# CC2530.net
KiCad netlist of a schematic drawn in Altium Designer
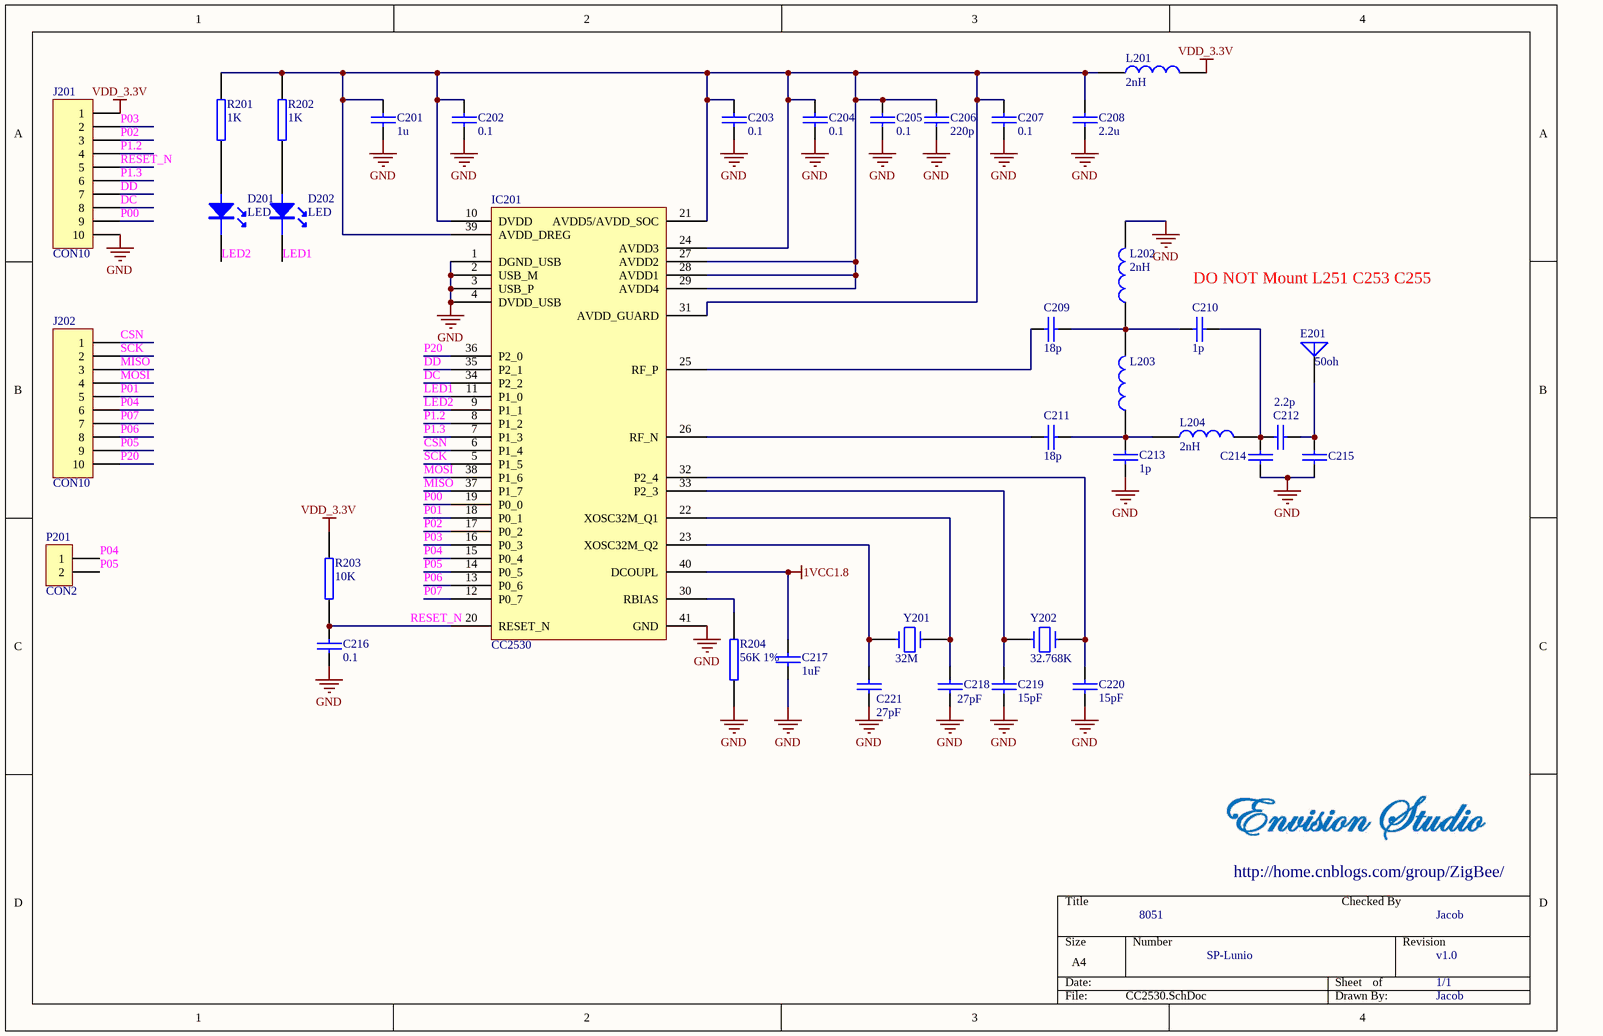
[diagram p0: CC2530.SchDoc]

(export (version "E")
  (design (tool "Eeschema 10.0.6"))
  (components
    (comp (ref "C201")
      (value "1u")
      (footprint "0402")
      (description "Capacitor")
      (libsource (lib "Miscellaneous Devices") (part "CAP"))
    )
    (comp (ref "C202")
      (value "0.1")
      (footprint "0402")
      (description "Capacitor")
      (libsource (lib "Miscellaneous Devices") (part "CAP"))
    )
    (comp (ref "C203")
      (value "0.1")
      (footprint "0402")
      (description "Capacitor")
      (libsource (lib "Miscellaneous Devices") (part "CAP"))
    )
    (comp (ref "C204")
      (value "0.1")
      (footprint "0402")
      (description "Capacitor")
      (libsource (lib "Miscellaneous Devices") (part "CAP"))
    )
    (comp (ref "C205")
      (value "0.1")
      (footprint "0402")
      (description "Capacitor")
      (libsource (lib "Miscellaneous Devices") (part "CAP"))
    )
    (comp (ref "C206")
      (value "220p")
      (footprint "0402")
      (description "Capacitor")
      (libsource (lib "Miscellaneous Devices") (part "CAP"))
    )
    (comp (ref "C207")
      (value "0.1")
      (footprint "0402")
      (description "Capacitor")
      (libsource (lib "Miscellaneous Devices") (part "CAP"))
    )
    (comp (ref "C208")
      (value "2.2u")
      (footprint "0402")
      (description "Capacitor")
      (libsource (lib "Miscellaneous Devices") (part "CAP"))
    )
    (comp (ref "C209")
      (value "18p")
      (footprint "0402")
      (description "Capacitor")
      (libsource (lib "Miscellaneous Devices") (part "CAP"))
    )
    (comp (ref "C210")
      (value "1p")
      (footprint "0402")
      (description "Capacitor")
      (libsource (lib "Miscellaneous Devices") (part "CAP"))
    )
    (comp (ref "C211")
      (value "18p")
      (footprint "0402")
      (description "Capacitor")
      (libsource (lib "Miscellaneous Devices") (part "CAP"))
    )
    (comp (ref "C212")
      (value "2.2p")
      (footprint "0402")
      (description "Capacitor")
      (libsource (lib "Miscellaneous Devices") (part "CAP"))
    )
    (comp (ref "C213")
      (value "1p")
      (footprint "0402")
      (description "Capacitor")
      (libsource (lib "Miscellaneous Devices") (part "CAP"))
    )
    (comp (ref "C214")
      (value "~")
      (footprint "0402")
      (description "Capacitor")
      (libsource (lib "Miscellaneous Devices") (part "CAP"))
    )
    (comp (ref "C215")
      (value "~")
      (footprint "0402")
      (description "Capacitor")
      (libsource (lib "Miscellaneous Devices") (part "CAP"))
    )
    (comp (ref "C216")
      (value "0.1")
      (footprint "0402")
      (description "Capacitor")
      (libsource (lib "Miscellaneous Devices") (part "CAP"))
    )
    (comp (ref "C217")
      (value "1uF")
      (footprint "0402")
      (description "Capacitor")
      (libsource (lib "Miscellaneous Devices") (part "CAP"))
    )
    (comp (ref "C218")
      (value "27pF")
      (footprint "0402")
      (description "Capacitor")
      (libsource (lib "Miscellaneous Devices") (part "CAP"))
    )
    (comp (ref "C219")
      (value "15pF")
      (footprint "0402")
      (description "Capacitor")
      (libsource (lib "Miscellaneous Devices") (part "CAP"))
    )
    (comp (ref "C220")
      (value "15pF")
      (footprint "0402")
      (description "Capacitor")
      (libsource (lib "Miscellaneous Devices") (part "CAP"))
    )
    (comp (ref "C221")
      (value "27pF")
      (footprint "0402")
      (description "Capacitor")
      (libsource (lib "Miscellaneous Devices") (part "CAP"))
    )
    (comp (ref "D201")
      (value "LED")
      (footprint "LED-0603")
      (libsource (lib "Miscellaneous Devices") (part "LED"))
    )
    (comp (ref "D202")
      (value "LED")
      (footprint "LED-0603")
      (libsource (lib "Miscellaneous Devices") (part "LED"))
    )
    (comp (ref "E201")
      (value "50oh")
      (footprint "ANT")
      (description "Generic Antenna")
      (libsource (lib "Miscellaneous Devices") (part "ANTENNA"))
    )
    (comp (ref "IC201") (value "CC2530") (footprint "PVQFN-N40") (libsource (lib "集成") (part "CC2530")))
    (comp (ref "J201")
      (value "CON10")
      (footprint "SIP10-2.0")
      (description "Connector")
      (libsource (lib "Miscellaneous Devices") (part "CON10"))
    )
    (comp (ref "J202")
      (value "CON10")
      (footprint "SIP10-2.0")
      (description "Connector")
      (libsource (lib "Miscellaneous Devices") (part "CON10"))
    )
    (comp (ref "L201")
      (value "2nH")
      (footprint "0402")
      (libsource (lib "Miscellaneous Devices") (part "INDUCTOR"))
    )
    (comp (ref "L202")
      (value "2nH")
      (footprint "0402")
      (libsource (lib "Miscellaneous Devices") (part "INDUCTOR"))
    )
    (comp (ref "L203")
      (value "~")
      (footprint "0402")
      (libsource (lib "Miscellaneous Devices") (part "INDUCTOR"))
    )
    (comp (ref "L204")
      (value "2nH")
      (footprint "0402")
      (libsource (lib "Miscellaneous Devices") (part "INDUCTOR"))
    )
    (comp (ref "P201")
      (value "CON2")
      (footprint "SIP2")
      (description "Connector")
      (libsource (lib "Miscellaneous Devices_99se") (part "CON2"))
    )
    (comp (ref "R201")
      (value "1K")
      (footprint "0402")
      (libsource (lib "Miscellaneous Devices") (part "RES2"))
    )
    (comp (ref "R202")
      (value "1K")
      (footprint "0402")
      (libsource (lib "Miscellaneous Devices") (part "RES2"))
    )
    (comp (ref "R203")
      (value "10K")
      (footprint "0402")
      (libsource (lib "Miscellaneous Devices") (part "RES2"))
    )
    (comp (ref "R204")
      (value "56K 1%")
      (footprint "0402")
      (libsource (lib "Miscellaneous Devices") (part "RES2"))
    )
    (comp (ref "Y201")
      (value "32M")
      (footprint "XT-SMD3225")
      (description "Crystal")
      (libsource (lib "Miscellaneous Devices") (part "CRYSTAL"))
    )
    (comp (ref "Y202")
      (value "32.768K")
      (footprint "XT_3")
      (description "Crystal")
      (libsource (lib "Miscellaneous Devices") (part "CRYSTAL"))
    )
  )
  (nets
    (net (code "1") (name "/CSN") (class "Default")
      (node (ref "IC201") (pin "6") (pinfunction "P1_4_6") (pintype "passive"))
      (node (ref "J202") (pin "1") (pinfunction "1_1") (pintype "passive"))
    )
    (net (code "2") (name "/DC") (class "Default")
      (node (ref "IC201") (pin "34") (pinfunction "P2_2_34") (pintype "passive"))
      (node (ref "J201") (pin "8") (pinfunction "8_8") (pintype "passive"))
    )
    (net (code "3") (name "/DD") (class "Default")
      (node (ref "IC201") (pin "35") (pinfunction "P2_1_35") (pintype "passive"))
      (node (ref "J201") (pin "7") (pinfunction "7_7") (pintype "passive"))
    )
    (net (code "4") (name "/LED1") (class "Default")
      (node (ref "D202") (pin "K") (pinfunction "2_K") (pintype "passive"))
      (node (ref "IC201") (pin "11") (pinfunction "P1_0_11") (pintype "passive"))
    )
    (net (code "5") (name "/LED2") (class "Default")
      (node (ref "D201") (pin "K") (pinfunction "2_K") (pintype "passive"))
      (node (ref "IC201") (pin "9") (pinfunction "P1_1_9") (pintype "passive"))
    )
    (net (code "6") (name "/MISO") (class "Default")
      (node (ref "IC201") (pin "37") (pinfunction "P1_7_37") (pintype "passive"))
      (node (ref "J202") (pin "3") (pinfunction "3_3") (pintype "passive"))
    )
    (net (code "7") (name "/MOSI") (class "Default")
      (node (ref "IC201") (pin "38") (pinfunction "P1_6_38") (pintype "passive"))
      (node (ref "J202") (pin "4") (pinfunction "4_4") (pintype "passive"))
    )
    (net (code "8") (name "/P00") (class "Default")
      (node (ref "IC201") (pin "19") (pinfunction "P0_0_19") (pintype "passive"))
      (node (ref "J201") (pin "9") (pinfunction "9_9") (pintype "passive"))
    )
    (net (code "9") (name "/P01") (class "Default")
      (node (ref "IC201") (pin "18") (pinfunction "P0_1_18") (pintype "passive"))
      (node (ref "J202") (pin "5") (pinfunction "5_5") (pintype "passive"))
    )
    (net (code "10") (name "/P1.2") (class "Default")
      (node (ref "IC201") (pin "8") (pinfunction "P1_2_8") (pintype "passive"))
      (node (ref "J201") (pin "4") (pinfunction "4_4") (pintype "passive"))
    )
    (net (code "11") (name "/P1.3") (class "Default")
      (node (ref "IC201") (pin "7") (pinfunction "P1_3_7") (pintype "passive"))
      (node (ref "J201") (pin "6") (pinfunction "6_6") (pintype "passive"))
    )
    (net (code "12") (name "/P02") (class "Default")
      (node (ref "IC201") (pin "17") (pinfunction "P0_2_17") (pintype "passive"))
      (node (ref "J201") (pin "3") (pinfunction "3_3") (pintype "passive"))
    )
    (net (code "13") (name "/P03") (class "Default")
      (node (ref "IC201") (pin "16") (pinfunction "P0_3_16") (pintype "passive"))
      (node (ref "J201") (pin "2") (pinfunction "2_2") (pintype "passive"))
    )
    (net (code "14") (name "/P04") (class "Default")
      (node (ref "IC201") (pin "15") (pinfunction "P0_4_15") (pintype "passive"))
      (node (ref "J202") (pin "6") (pinfunction "6_6") (pintype "passive"))
      (node (ref "P201") (pin "1") (pinfunction "1_1") (pintype "passive"))
    )
    (net (code "15") (name "/P05") (class "Default")
      (node (ref "IC201") (pin "14") (pinfunction "P0_5_14") (pintype "passive"))
      (node (ref "J202") (pin "9") (pinfunction "9_9") (pintype "passive"))
      (node (ref "P201") (pin "2") (pinfunction "2_2") (pintype "passive"))
    )
    (net (code "16") (name "/P06") (class "Default")
      (node (ref "IC201") (pin "13") (pinfunction "P0_6_13") (pintype "passive"))
      (node (ref "J202") (pin "8") (pinfunction "8_8") (pintype "passive"))
    )
    (net (code "17") (name "/P07") (class "Default")
      (node (ref "IC201") (pin "12") (pinfunction "P0_7_12") (pintype "passive"))
      (node (ref "J202") (pin "7") (pinfunction "7_7") (pintype "passive"))
    )
    (net (code "18") (name "/P20") (class "Default")
      (node (ref "IC201") (pin "36") (pinfunction "P2_0_36") (pintype "passive"))
      (node (ref "J202") (pin "10") (pinfunction "10_10") (pintype "passive"))
    )
    (net (code "19") (name "/RESET_N") (class "Default")
      (node (ref "C216") (pin "1") (pinfunction "1_1") (pintype "passive"))
      (node (ref "IC201") (pin "20") (pinfunction "RESET_N_20") (pintype "passive"))
      (node (ref "J201") (pin "5") (pinfunction "5_5") (pintype "passive"))
      (node (ref "R203") (pin "1") (pinfunction "1_1") (pintype "passive"))
    )
    (net (code "20") (name "/SCK") (class "Default")
      (node (ref "IC201") (pin "5") (pinfunction "P1_5_5") (pintype "passive"))
      (node (ref "J202") (pin "2") (pinfunction "2_2") (pintype "passive"))
    )
    (net (code "21") (name "1VCC1.8") (class "Default")
      (node (ref "C217") (pin "1") (pinfunction "1_1") (pintype "passive"))
      (node (ref "IC201") (pin "40") (pinfunction "DCOUPL_40") (pintype "passive"))
    )
    (net (code "22") (name "GND") (class "Default")
      (node (ref "C201") (pin "2") (pinfunction "2_2") (pintype "passive"))
      (node (ref "C202") (pin "2") (pinfunction "2_2") (pintype "passive"))
      (node (ref "C203") (pin "2") (pinfunction "2_2") (pintype "passive"))
      (node (ref "C204") (pin "2") (pinfunction "2_2") (pintype "passive"))
      (node (ref "C205") (pin "2") (pinfunction "2_2") (pintype "passive"))
      (node (ref "C206") (pin "2") (pinfunction "2_2") (pintype "passive"))
      (node (ref "C207") (pin "2") (pinfunction "2_2") (pintype "passive"))
      (node (ref "C208") (pin "2") (pinfunction "2_2") (pintype "passive"))
      (node (ref "C213") (pin "2") (pinfunction "2_2") (pintype "passive"))
      (node (ref "C214") (pin "2") (pinfunction "2_2") (pintype "passive"))
      (node (ref "C215") (pin "1") (pinfunction "1_1") (pintype "passive"))
      (node (ref "C216") (pin "2") (pinfunction "2_2") (pintype "passive"))
      (node (ref "C217") (pin "2") (pinfunction "2_2") (pintype "passive"))
      (node (ref "C218") (pin "2") (pinfunction "2_2") (pintype "passive"))
      (node (ref "C219") (pin "2") (pinfunction "2_2") (pintype "passive"))
      (node (ref "C220") (pin "2") (pinfunction "2_2") (pintype "passive"))
      (node (ref "C221") (pin "2") (pinfunction "2_2") (pintype "passive"))
      (node (ref "IC201") (pin "1") (pinfunction "DGND_USB_1") (pintype "passive"))
      (node (ref "IC201") (pin "2") (pinfunction "USB_M_2") (pintype "passive"))
      (node (ref "IC201") (pin "3") (pinfunction "USB_P_3") (pintype "passive"))
      (node (ref "IC201") (pin "4") (pinfunction "DVDD_USB_4") (pintype "passive"))
      (node (ref "IC201") (pin "41") (pinfunction "GND_41") (pintype "passive"))
      (node (ref "J201") (pin "10") (pinfunction "10_10") (pintype "passive"))
      (node (ref "L202") (pin "2") (pinfunction "2_2") (pintype "passive"))
      (node (ref "R204") (pin "2") (pinfunction "2_2") (pintype "passive"))
    )
    (net (code "23") (name "Net-(C209-Pad2)") (class "Default")
      (node (ref "C209") (pin "2") (pinfunction "2_2") (pintype "passive"))
      (node (ref "C210") (pin "1") (pinfunction "1_1") (pintype "passive"))
      (node (ref "L202") (pin "1") (pinfunction "1_1") (pintype "passive"))
      (node (ref "L203") (pin "2") (pinfunction "2_2") (pintype "passive"))
    )
    (net (code "24") (name "Net-(C210-Pad2)") (class "Default")
      (node (ref "C210") (pin "2") (pinfunction "2_2") (pintype "passive"))
      (node (ref "C212") (pin "1") (pinfunction "1_1") (pintype "passive"))
      (node (ref "C214") (pin "1") (pinfunction "1_1") (pintype "passive"))
      (node (ref "L204") (pin "2") (pinfunction "2_2") (pintype "passive"))
    )
    (net (code "25") (name "Net-(C211-Pad2)") (class "Default")
      (node (ref "C211") (pin "2") (pinfunction "2_2") (pintype "passive"))
      (node (ref "C213") (pin "1") (pinfunction "1_1") (pintype "passive"))
      (node (ref "L203") (pin "1") (pinfunction "1_1") (pintype "passive"))
      (node (ref "L204") (pin "1") (pinfunction "1_1") (pintype "passive"))
    )
    (net (code "26") (name "Net-(D201-1)") (class "Default")
      (node (ref "D201") (pin "A") (pinfunction "1_A") (pintype "passive"))
      (node (ref "R201") (pin "1") (pinfunction "1_1") (pintype "passive"))
    )
    (net (code "27") (name "Net-(D202-1)") (class "Default")
      (node (ref "D202") (pin "A") (pinfunction "1_A") (pintype "passive"))
      (node (ref "R202") (pin "1") (pinfunction "1_1") (pintype "passive"))
    )
    (net (code "28") (name "Net-(E201-A)") (class "Default")
      (node (ref "C212") (pin "2") (pinfunction "2_2") (pintype "passive"))
      (node (ref "C215") (pin "2") (pinfunction "2_2") (pintype "passive"))
      (node (ref "E201") (pin "1") (pinfunction "A_1") (pintype "passive"))
    )
    (net (code "29") (name "Net-(IC201-AVDD1)") (class "Default")
      (node (ref "C201") (pin "1") (pinfunction "1_1") (pintype "passive"))
      (node (ref "C202") (pin "1") (pinfunction "1_1") (pintype "passive"))
      (node (ref "C203") (pin "1") (pinfunction "1_1") (pintype "passive"))
      (node (ref "C204") (pin "1") (pinfunction "1_1") (pintype "passive"))
      (node (ref "C205") (pin "1") (pinfunction "1_1") (pintype "passive"))
      (node (ref "C206") (pin "1") (pinfunction "1_1") (pintype "passive"))
      (node (ref "C207") (pin "1") (pinfunction "1_1") (pintype "passive"))
      (node (ref "C208") (pin "1") (pinfunction "1_1") (pintype "passive"))
      (node (ref "IC201") (pin "10") (pinfunction "DVDD_10") (pintype "passive"))
      (node (ref "IC201") (pin "21") (pinfunction "AVDD5/AVDD_SOC_21") (pintype "passive"))
      (node (ref "IC201") (pin "24") (pinfunction "AVDD3_24") (pintype "passive"))
      (node (ref "IC201") (pin "27") (pinfunction "AVDD2_27") (pintype "passive"))
      (node (ref "IC201") (pin "28") (pinfunction "AVDD1_28") (pintype "passive"))
      (node (ref "IC201") (pin "29") (pinfunction "AVDD4_29") (pintype "passive"))
      (node (ref "IC201") (pin "31") (pinfunction "AVDD_GUARD_31") (pintype "passive"))
      (node (ref "IC201") (pin "39") (pinfunction "AVDD_DREG_39") (pintype "passive"))
      (node (ref "L201") (pin "1") (pinfunction "1_1") (pintype "passive"))
      (node (ref "R201") (pin "2") (pinfunction "2_2") (pintype "passive"))
      (node (ref "R202") (pin "2") (pinfunction "2_2") (pintype "passive"))
    )
    (net (code "30") (name "Net-(IC201-P2_3)") (class "Default")
      (node (ref "C219") (pin "1") (pinfunction "1_1") (pintype "passive"))
      (node (ref "IC201") (pin "33") (pinfunction "P2_3_33") (pintype "passive"))
      (node (ref "Y202") (pin "2") (pinfunction "2_2") (pintype "passive"))
    )
    (net (code "31") (name "Net-(IC201-P2_4)") (class "Default")
      (node (ref "C220") (pin "1") (pinfunction "1_1") (pintype "passive"))
      (node (ref "IC201") (pin "32") (pinfunction "P2_4_32") (pintype "passive"))
      (node (ref "Y202") (pin "1") (pinfunction "1_1") (pintype "passive"))
    )
    (net (code "32") (name "Net-(IC201-RBIAS)") (class "Default")
      (node (ref "IC201") (pin "30") (pinfunction "RBIAS_30") (pintype "passive"))
      (node (ref "R204") (pin "1") (pinfunction "1_1") (pintype "passive"))
    )
    (net (code "33") (name "Net-(IC201-RF_N)") (class "Default")
      (node (ref "C211") (pin "1") (pinfunction "1_1") (pintype "passive"))
      (node (ref "IC201") (pin "26") (pinfunction "RF_N_26") (pintype "passive"))
    )
    (net (code "34") (name "Net-(IC201-RF_P)") (class "Default")
      (node (ref "C209") (pin "1") (pinfunction "1_1") (pintype "passive"))
      (node (ref "IC201") (pin "25") (pinfunction "RF_P_25") (pintype "passive"))
    )
    (net (code "35") (name "Net-(IC201-XOSC32M_Q1)") (class "Default")
      (node (ref "C218") (pin "1") (pinfunction "1_1") (pintype "passive"))
      (node (ref "IC201") (pin "22") (pinfunction "XOSC32M_Q1_22") (pintype "passive"))
      (node (ref "Y201") (pin "2") (pinfunction "2_2") (pintype "passive"))
    )
    (net (code "36") (name "Net-(IC201-XOSC32M_Q2)") (class "Default")
      (node (ref "C221") (pin "1") (pinfunction "1_1") (pintype "passive"))
      (node (ref "IC201") (pin "23") (pinfunction "XOSC32M_Q2_23") (pintype "passive"))
      (node (ref "Y201") (pin "1") (pinfunction "1_1") (pintype "passive"))
    )
    (net (code "37") (name "VDD_3.3V") (class "Default")
      (node (ref "J201") (pin "1") (pinfunction "1_1") (pintype "passive"))
      (node (ref "L201") (pin "2") (pinfunction "2_2") (pintype "passive"))
      (node (ref "R203") (pin "2") (pinfunction "2_2") (pintype "passive"))
    )
  )
)
